# ad3.net
KiCad netlist of a schematic drawn in Altium Designer
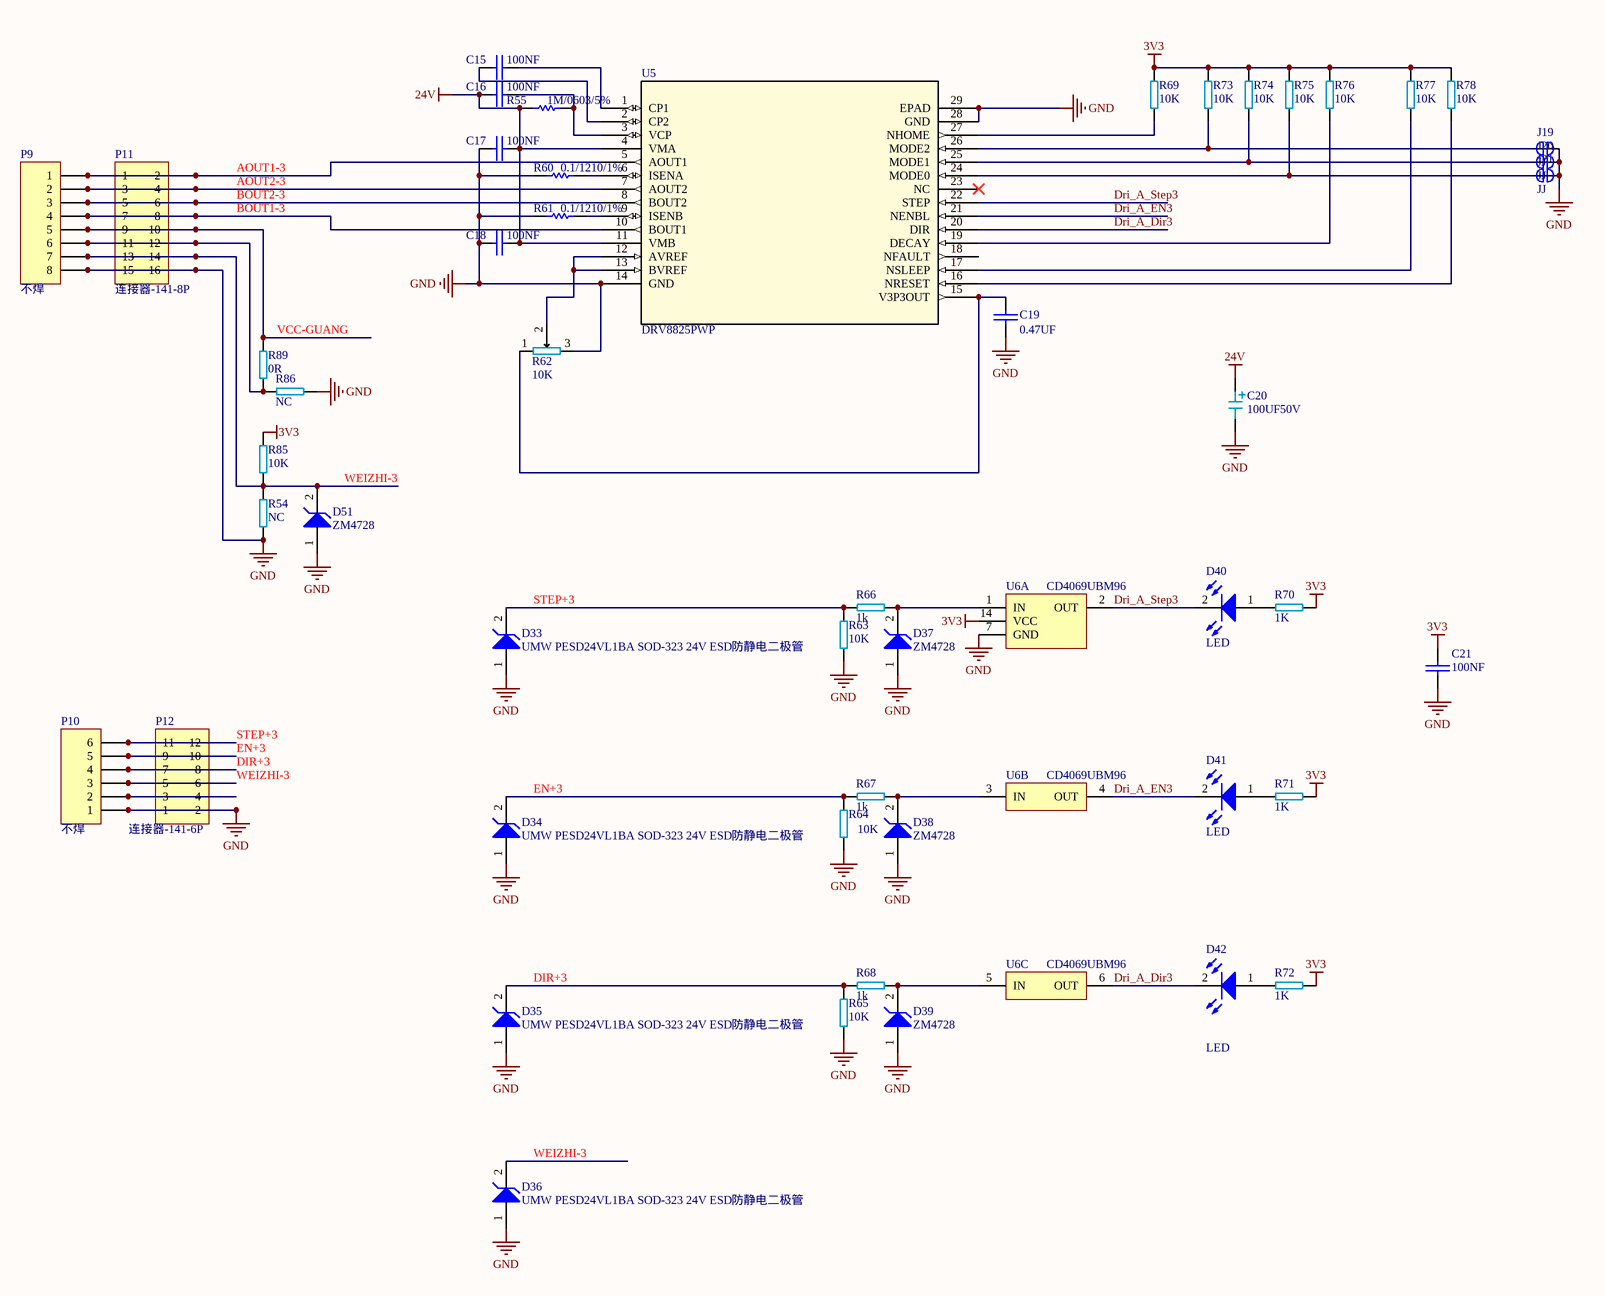
[diagram p0: ad3.SchDoc]

(export (version "E")
  (design (tool "Eeschema 10.0.6"))
  (components
    (comp (ref "C15")
      (value "100NF")
      (footprint "C0603")
      (description "Capacitor")
      (libsource (lib "Miscellaneous Devices") (part "CAP"))
    )
    (comp (ref "C16")
      (value "100NF")
      (footprint "C0603")
      (description "Capacitor")
      (libsource (lib "Miscellaneous Devices") (part "CAP"))
    )
    (comp (ref "C17")
      (value "100NF")
      (footprint "C0603")
      (description "Capacitor")
      (libsource (lib "Miscellaneous Devices") (part "CAP"))
    )
    (comp (ref "C18")
      (value "100NF")
      (footprint "C0603")
      (description "Capacitor")
      (libsource (lib "Miscellaneous Devices") (part "CAP"))
    )
    (comp (ref "C19")
      (value "0.47UF")
      (footprint "C0603")
      (description "Capacitor")
      (libsource (lib "Miscellaneous Devices") (part "CAP"))
    )
    (comp (ref "C20")
      (value "100UF50V")
      (footprint "CE8")
      (description "铝电解电容")
      (libsource (lib "base") (part "C+"))
    )
    (comp (ref "C21")
      (value "100NF")
      (footprint "C0603")
      (description "Capacitor")
      (libsource (lib "Miscellaneous Devices") (part "CAP"))
    )
    (comp (ref "D33")
      (value "UMW PESD24VL1BA SOD-323 24V ESD防静电二极管")
      (footprint "SOD323")
      (description "稳压管")
      (fields (field (name "PUBLISHER") "Altium Limited"))
      (libsource (lib "base") (part "TVS-SMA"))
    )
    (comp (ref "D34")
      (value "UMW PESD24VL1BA SOD-323 24V ESD防静电二极管")
      (footprint "SOD323")
      (description "稳压管")
      (fields (field (name "PUBLISHER") "Altium Limited"))
      (libsource (lib "base") (part "TVS-SMA"))
    )
    (comp (ref "D35")
      (value "UMW PESD24VL1BA SOD-323 24V ESD防静电二极管")
      (footprint "SOD323")
      (description "稳压管")
      (fields (field (name "PUBLISHER") "Altium Limited"))
      (libsource (lib "base") (part "TVS-SMA"))
    )
    (comp (ref "D36")
      (value "UMW PESD24VL1BA SOD-323 24V ESD防静电二极管")
      (footprint "SOD323")
      (description "稳压管")
      (fields (field (name "PUBLISHER") "Altium Limited"))
      (libsource (lib "base") (part "TVS-SMA"))
    )
    (comp (ref "D37")
      (value "ZM4728")
      (footprint "D1206")
      (description "稳压管")
      (fields (field (name "PUBLISHER") "Altium Limited"))
      (libsource (lib "base") (part "TVS-SMA"))
    )
    (comp (ref "D38")
      (value "ZM4728")
      (footprint "D1206")
      (description "稳压管")
      (fields (field (name "PUBLISHER") "Altium Limited"))
      (libsource (lib "base") (part "TVS-SMA"))
    )
    (comp (ref "D39")
      (value "ZM4728")
      (footprint "D1206")
      (description "稳压管")
      (fields (field (name "PUBLISHER") "Altium Limited"))
      (libsource (lib "base") (part "TVS-SMA"))
    )
    (comp (ref "D40")
      (value "LED")
      (footprint "LED0603")
      (description "LED0603")
      (fields (field (name "PUBLISHER") "Altium Limited"))
      (libsource (lib "base") (part "LED0603"))
    )
    (comp (ref "D41")
      (value "LED")
      (footprint "LED0603")
      (description "LED0603")
      (fields (field (name "PUBLISHER") "Altium Limited"))
      (libsource (lib "base") (part "LED0603"))
    )
    (comp (ref "D42")
      (value "LED")
      (footprint "LED0603")
      (description "LED0603")
      (fields (field (name "PUBLISHER") "Altium Limited"))
      (libsource (lib "base") (part "LED0603"))
    )
    (comp (ref "D51")
      (value "ZM4728")
      (footprint "D1206")
      (description "稳压管")
      (fields (field (name "PUBLISHER") "Altium Limited"))
      (libsource (lib "base") (part "TVS-SMA"))
    )
    (comp (ref "J19")
      (value "JJ")
      (footprint "TIAOXIAN-PAN")
      (description "跳线")
      (libsource (lib "base") (part "JJ"))
    )
    (comp (ref "J20")
      (value "JJ")
      (footprint "TIAOXIAN-PAN")
      (description "跳线")
      (libsource (lib "base") (part "JJ"))
    )
    (comp (ref "J21")
      (value "JJ")
      (footprint "TIAOXIAN-PAN")
      (description "跳线")
      (libsource (lib "base") (part "JJ"))
    )
    (comp (ref "P9")
      (value "不焊")
      (footprint "SIP8")
      (description "连接器")
      (fields (field (name "PUBLISHER") "Altium Limited"))
      (libsource (lib "base") (part "SIP8"))
    )
    (comp (ref "P10")
      (value "不焊")
      (footprint "SIP6")
      (description "连接器")
      (fields (field (name "PUBLISHER") "Altium Limited"))
      (libsource (lib "base") (part "SIP6"))
    )
    (comp (ref "P11")
      (value "连接器-141-8P")
      (footprint "141V-8P")
      (description "连接器")
      (fields (field (name "PUBLISHER") "Altium Limited"))
      (libsource (lib "base") (part "DIC16"))
    )
    (comp (ref "P12")
      (value "连接器-141-6P")
      (footprint "141V-6P")
      (description "连接器")
      (fields (field (name "PUBLISHER") "Altium Limited"))
      (libsource (lib "base") (part "DIC12"))
    )
    (comp (ref "R54")
      (value "NC")
      (footprint "R0603")
      (description "贴片电阻")
      (libsource (lib "base") (part "R-0603"))
    )
    (comp (ref "R55")
      (value "1M/0603/5%")
      (footprint "R0603")
      (description "Resistor")
      (fields (field (name "PUBLISHER") "Altium Limited"))
      (libsource (lib "Miscellaneous Devices") (part "Res1"))
    )
    (comp (ref "R60")
      (value "0.1/1210/1%")
      (footprint "R1210")
      (description "Resistor")
      (fields (field (name "PUBLISHER") "Altium Limited"))
      (libsource (lib "Miscellaneous Devices") (part "Res1"))
    )
    (comp (ref "R61")
      (value "0.1/1210/1%")
      (footprint "R1210")
      (description "Resistor")
      (fields (field (name "PUBLISHER") "Altium Limited"))
      (libsource (lib "Miscellaneous Devices") (part "Res1"))
    )
    (comp (ref "R62")
      (value "10K")
      (footprint "RR-MINI-SMD")
      (description "电位器")
      (libsource (lib "base") (part "RR"))
    )
    (comp (ref "R63")
      (value "10K")
      (footprint "R0603")
      (description "贴片电阻")
      (libsource (lib "base") (part "R-0603"))
    )
    (comp (ref "R64")
      (value "10K")
      (footprint "R0603")
      (description "贴片电阻")
      (libsource (lib "base") (part "R-0603"))
    )
    (comp (ref "R65")
      (value "10K")
      (footprint "R0603")
      (description "贴片电阻")
      (libsource (lib "base") (part "R-0603"))
    )
    (comp (ref "R66")
      (value "1k")
      (footprint "R0603")
      (description "贴片电阻")
      (libsource (lib "base") (part "R-0603"))
    )
    (comp (ref "R67")
      (value "1k")
      (footprint "R0603")
      (description "贴片电阻")
      (libsource (lib "base") (part "R-0603"))
    )
    (comp (ref "R68")
      (value "1k")
      (footprint "R0603")
      (description "贴片电阻")
      (libsource (lib "base") (part "R-0603"))
    )
    (comp (ref "R69")
      (value "10K")
      (footprint "R0603")
      (description "贴片电阻")
      (libsource (lib "base") (part "R-0603"))
    )
    (comp (ref "R70")
      (value "1K")
      (footprint "R0603")
      (description "贴片电阻")
      (libsource (lib "base") (part "R-0603"))
    )
    (comp (ref "R71")
      (value "1K")
      (footprint "R0603")
      (description "贴片电阻")
      (libsource (lib "base") (part "R-0603"))
    )
    (comp (ref "R72")
      (value "1K")
      (footprint "R0603")
      (description "贴片电阻")
      (libsource (lib "base") (part "R-0603"))
    )
    (comp (ref "R73")
      (value "10K")
      (footprint "R0603")
      (description "贴片电阻")
      (libsource (lib "base") (part "R-0603"))
    )
    (comp (ref "R74")
      (value "10K")
      (footprint "R0603")
      (description "贴片电阻")
      (libsource (lib "base") (part "R-0603"))
    )
    (comp (ref "R75")
      (value "10K")
      (footprint "R0603")
      (description "贴片电阻")
      (libsource (lib "base") (part "R-0603"))
    )
    (comp (ref "R76")
      (value "10K")
      (footprint "R0603")
      (description "贴片电阻")
      (libsource (lib "base") (part "R-0603"))
    )
    (comp (ref "R77")
      (value "10K")
      (footprint "R0603")
      (description "贴片电阻")
      (libsource (lib "base") (part "R-0603"))
    )
    (comp (ref "R78")
      (value "10K")
      (footprint "R0603")
      (description "贴片电阻")
      (libsource (lib "base") (part "R-0603"))
    )
    (comp (ref "R85")
      (value "10K")
      (footprint "R0603")
      (description "贴片电阻")
      (libsource (lib "base") (part "R-0603"))
    )
    (comp (ref "R86")
      (value "NC")
      (footprint "R0603")
      (description "贴片电阻")
      (libsource (lib "base") (part "R-0603"))
    )
    (comp (ref "R89")
      (value "0R")
      (footprint "R0603")
      (description "贴片电阻")
      (libsource (lib "base") (part "R-0603"))
    )
    (comp (ref "U5")
      (value "DRV8825PWP")
      (footprint "HTSSOP28")
      (description "芯片")
      (libsource (lib "User") (part "DRV8825PWP"))
    )
    (comp (ref "U6")
      (value "CD4069UBM96")
      (footprint "SO14")
      (description "芯片")
      (libsource (lib "Chip") (part "CD4069"))
    )
  )
  (nets
    (net (code "1") (name "/AOUT1-3") (class "Default")
      (node (ref "P11") (pin "1") (pinfunction "1_1") (pintype "passive"))
      (node (ref "P11") (pin "2") (pinfunction "2_2") (pintype "passive"))
      (node (ref "P9") (pin "1") (pinfunction "1_1") (pintype "passive"))
      (node (ref "U5") (pin "5") (pinfunction "AOUT1_5") (pintype "output"))
    )
    (net (code "2") (name "/AOUT2-3") (class "Default")
      (node (ref "P11") (pin "3") (pinfunction "3_3") (pintype "passive"))
      (node (ref "P11") (pin "4") (pinfunction "4_4") (pintype "passive"))
      (node (ref "P9") (pin "2") (pinfunction "2_2") (pintype "passive"))
      (node (ref "U5") (pin "7") (pinfunction "AOUT2_7") (pintype "output"))
    )
    (net (code "3") (name "/BOUT1-3") (class "Default")
      (node (ref "P11") (pin "7") (pinfunction "7_7") (pintype "passive"))
      (node (ref "P11") (pin "8") (pinfunction "8_8") (pintype "passive"))
      (node (ref "P9") (pin "4") (pinfunction "4_4") (pintype "passive"))
      (node (ref "U5") (pin "10") (pinfunction "BOUT1_10") (pintype "output"))
    )
    (net (code "4") (name "/BOUT2-3") (class "Default")
      (node (ref "P11") (pin "5") (pinfunction "5_5") (pintype "passive"))
      (node (ref "P11") (pin "6") (pinfunction "6_6") (pintype "passive"))
      (node (ref "P9") (pin "3") (pinfunction "3_3") (pintype "passive"))
      (node (ref "U5") (pin "8") (pinfunction "BOUT2_8") (pintype "output"))
    )
    (net (code "5") (name "/DIR+3") (class "Default")
      (node (ref "D35") (pin "2") (pinfunction "2_2") (pintype "passive"))
      (node (ref "P10") (pin "4") (pinfunction "4_4") (pintype "passive"))
      (node (ref "P12") (pin "7") (pinfunction "7_7") (pintype "passive"))
      (node (ref "P12") (pin "8") (pinfunction "8_8") (pintype "passive"))
      (node (ref "R65") (pin "2") (pinfunction "2_2") (pintype "passive"))
      (node (ref "R68") (pin "2") (pinfunction "2_2") (pintype "passive"))
    )
    (net (code "6") (name "/Dri_A_Dir3") (class "Default")
      (node (ref "D42") (pin "2") (pinfunction "K_2") (pintype "passive"))
      (node (ref "U5") (pin "20") (pinfunction "DIR_20") (pintype "input"))
      (node (ref "U6") (pin "6") (pinfunction "OUT_6") (pintype "passive"))
    )
    (net (code "7") (name "/Dri_A_EN3") (class "Default")
      (node (ref "D41") (pin "2") (pinfunction "K_2") (pintype "passive"))
      (node (ref "U5") (pin "21") (pinfunction "NENBL_21") (pintype "input"))
      (node (ref "U6") (pin "4") (pinfunction "OUT_4") (pintype "passive"))
    )
    (net (code "8") (name "/Dri_A_Step3") (class "Default")
      (node (ref "D40") (pin "2") (pinfunction "K_2") (pintype "passive"))
      (node (ref "U5") (pin "22") (pinfunction "STEP_22") (pintype "input"))
      (node (ref "U6") (pin "2") (pinfunction "OUT_2") (pintype "passive"))
    )
    (net (code "9") (name "/EN+3") (class "Default")
      (node (ref "D34") (pin "2") (pinfunction "2_2") (pintype "passive"))
      (node (ref "P10") (pin "5") (pinfunction "5_5") (pintype "passive"))
      (node (ref "P12") (pin "10") (pinfunction "10_10") (pintype "passive"))
      (node (ref "P12") (pin "9") (pinfunction "9_9") (pintype "passive"))
      (node (ref "R64") (pin "2") (pinfunction "2_2") (pintype "passive"))
      (node (ref "R67") (pin "2") (pinfunction "2_2") (pintype "passive"))
    )
    (net (code "10") (name "/STEP+3") (class "Default")
      (node (ref "D33") (pin "2") (pinfunction "2_2") (pintype "passive"))
      (node (ref "P10") (pin "6") (pinfunction "6_6") (pintype "passive"))
      (node (ref "P12") (pin "11") (pinfunction "11_11") (pintype "passive"))
      (node (ref "P12") (pin "12") (pinfunction "12_12") (pintype "passive"))
      (node (ref "R63") (pin "2") (pinfunction "2_2") (pintype "passive"))
      (node (ref "R66") (pin "2") (pinfunction "2_2") (pintype "passive"))
    )
    (net (code "11") (name "/VCC-GUANG") (class "Default")
      (node (ref "P11") (pin "10") (pinfunction "10_10") (pintype "passive"))
      (node (ref "P11") (pin "9") (pinfunction "9_9") (pintype "passive"))
      (node (ref "P9") (pin "5") (pinfunction "5_5") (pintype "passive"))
      (node (ref "R89") (pin "2") (pinfunction "2_2") (pintype "passive"))
    )
    (net (code "12") (name "/WEIZHI-3") (class "Default")
      (node (ref "D36") (pin "2") (pinfunction "2_2") (pintype "passive"))
      (node (ref "D51") (pin "2") (pinfunction "2_2") (pintype "passive"))
      (node (ref "P10") (pin "3") (pinfunction "3_3") (pintype "passive"))
      (node (ref "P11") (pin "13") (pinfunction "13_13") (pintype "passive"))
      (node (ref "P11") (pin "14") (pinfunction "14_14") (pintype "passive"))
      (node (ref "P12") (pin "5") (pinfunction "5_5") (pintype "passive"))
      (node (ref "P12") (pin "6") (pinfunction "6_6") (pintype "passive"))
      (node (ref "P9") (pin "7") (pinfunction "7_7") (pintype "passive"))
      (node (ref "R54") (pin "2") (pinfunction "2_2") (pintype "passive"))
      (node (ref "R85") (pin "1") (pinfunction "1_1") (pintype "passive"))
    )
    (net (code "13") (name "3V3") (class "Default")
      (node (ref "C21") (pin "2") (pinfunction "2_2") (pintype "passive"))
      (node (ref "R69") (pin "2") (pinfunction "2_2") (pintype "passive"))
      (node (ref "R70") (pin "2") (pinfunction "2_2") (pintype "passive"))
      (node (ref "R71") (pin "2") (pinfunction "2_2") (pintype "passive"))
      (node (ref "R72") (pin "2") (pinfunction "2_2") (pintype "passive"))
      (node (ref "R73") (pin "2") (pinfunction "2_2") (pintype "passive"))
      (node (ref "R74") (pin "2") (pinfunction "2_2") (pintype "passive"))
      (node (ref "R75") (pin "2") (pinfunction "2_2") (pintype "passive"))
      (node (ref "R76") (pin "2") (pinfunction "2_2") (pintype "passive"))
      (node (ref "R77") (pin "2") (pinfunction "2_2") (pintype "passive"))
      (node (ref "R78") (pin "2") (pinfunction "2_2") (pintype "passive"))
      (node (ref "R85") (pin "2") (pinfunction "2_2") (pintype "passive"))
      (node (ref "U6") (pin "14") (pinfunction "VCC_14") (pintype "passive"))
    )
    (net (code "14") (name "24V") (class "Default")
      (node (ref "C16") (pin "1") (pinfunction "1_1") (pintype "passive"))
      (node (ref "C17") (pin "2") (pinfunction "2_2") (pintype "passive"))
      (node (ref "C18") (pin "2") (pinfunction "2_2") (pintype "passive"))
      (node (ref "C20") (pin "1") (pinfunction "1_1") (pintype "passive"))
      (node (ref "R55") (pin "2") (pinfunction "2_2") (pintype "passive"))
      (node (ref "U5") (pin "11") (pinfunction "VMB_11") (pintype "power_in"))
      (node (ref "U5") (pin "4") (pinfunction "VMA_4") (pintype "power_in"))
    )
    (net (code "15") (name "GND") (class "Default")
      (node (ref "C17") (pin "1") (pinfunction "1_1") (pintype "passive"))
      (node (ref "C18") (pin "1") (pinfunction "1_1") (pintype "passive"))
      (node (ref "C19") (pin "1") (pinfunction "1_1") (pintype "passive"))
      (node (ref "C20") (pin "2") (pinfunction "2_2") (pintype "passive"))
      (node (ref "C21") (pin "1") (pinfunction "1_1") (pintype "passive"))
      (node (ref "D33") (pin "1") (pinfunction "1_1") (pintype "passive"))
      (node (ref "D34") (pin "1") (pinfunction "1_1") (pintype "passive"))
      (node (ref "D35") (pin "1") (pinfunction "1_1") (pintype "passive"))
      (node (ref "D36") (pin "1") (pinfunction "1_1") (pintype "passive"))
      (node (ref "D37") (pin "1") (pinfunction "1_1") (pintype "passive"))
      (node (ref "D38") (pin "1") (pinfunction "1_1") (pintype "passive"))
      (node (ref "D39") (pin "1") (pinfunction "1_1") (pintype "passive"))
      (node (ref "D51") (pin "1") (pinfunction "1_1") (pintype "passive"))
      (node (ref "J19") (pin "2") (pinfunction "2_2") (pintype "passive"))
      (node (ref "J20") (pin "2") (pinfunction "2_2") (pintype "passive"))
      (node (ref "J21") (pin "2") (pinfunction "2_2") (pintype "passive"))
      (node (ref "P10") (pin "1") (pinfunction "1_1") (pintype "passive"))
      (node (ref "P11") (pin "15") (pinfunction "15_15") (pintype "passive"))
      (node (ref "P11") (pin "16") (pinfunction "16_16") (pintype "passive"))
      (node (ref "P12") (pin "1") (pinfunction "1_1") (pintype "passive"))
      (node (ref "P12") (pin "2") (pinfunction "2_2") (pintype "passive"))
      (node (ref "P9") (pin "8") (pinfunction "8_8") (pintype "passive"))
      (node (ref "R54") (pin "1") (pinfunction "1_1") (pintype "passive"))
      (node (ref "R60") (pin "2") (pinfunction "2_2") (pintype "passive"))
      (node (ref "R61") (pin "2") (pinfunction "2_2") (pintype "passive"))
      (node (ref "R62") (pin "3") (pinfunction "3_3") (pintype "passive"))
      (node (ref "R63") (pin "1") (pinfunction "1_1") (pintype "passive"))
      (node (ref "R64") (pin "1") (pinfunction "1_1") (pintype "passive"))
      (node (ref "R65") (pin "1") (pinfunction "1_1") (pintype "passive"))
      (node (ref "R86") (pin "1") (pinfunction "1_1") (pintype "passive"))
      (node (ref "U5") (pin "14") (pinfunction "GND_14") (pintype "power_in"))
      (node (ref "U5") (pin "28") (pinfunction "GND_28") (pintype "power_in"))
      (node (ref "U5") (pin "29") (pinfunction "EPAD_29") (pintype "passive"))
      (node (ref "U6") (pin "7") (pinfunction "GND_7") (pintype "passive"))
    )
    (net (code "16") (name "Net-(D40-A)") (class "Default")
      (node (ref "D40") (pin "1") (pinfunction "A_1") (pintype "passive"))
      (node (ref "R70") (pin "1") (pinfunction "1_1") (pintype "passive"))
    )
    (net (code "17") (name "Net-(D41-A)") (class "Default")
      (node (ref "D41") (pin "1") (pinfunction "A_1") (pintype "passive"))
      (node (ref "R71") (pin "1") (pinfunction "1_1") (pintype "passive"))
    )
    (net (code "18") (name "Net-(D42-A)") (class "Default")
      (node (ref "D42") (pin "1") (pinfunction "A_1") (pintype "passive"))
      (node (ref "R72") (pin "1") (pinfunction "1_1") (pintype "passive"))
    )
    (net (code "19") (name "Net-(P10-Pad2)") (class "Default")
      (node (ref "P10") (pin "2") (pinfunction "2_2") (pintype "passive"))
      (node (ref "P12") (pin "3") (pinfunction "3_3") (pintype "passive"))
      (node (ref "P12") (pin "4") (pinfunction "4_4") (pintype "passive"))
    )
    (net (code "20") (name "Net-(P11-Pad11)") (class "Default")
      (node (ref "P11") (pin "11") (pinfunction "11_11") (pintype "passive"))
      (node (ref "P11") (pin "12") (pinfunction "12_12") (pintype "passive"))
      (node (ref "P9") (pin "6") (pinfunction "6_6") (pintype "passive"))
      (node (ref "R86") (pin "2") (pinfunction "2_2") (pintype "passive"))
      (node (ref "R89") (pin "1") (pinfunction "1_1") (pintype "passive"))
    )
    (net (code "21") (name "Net-(U5-AVREF)") (class "Default")
      (node (ref "R62") (pin "2") (pinfunction "2_2") (pintype "passive"))
      (node (ref "U5") (pin "12") (pinfunction "AVREF_12") (pintype "input"))
      (node (ref "U5") (pin "13") (pinfunction "BVREF_13") (pintype "input"))
    )
    (net (code "22") (name "Net-(U5-CP1)") (class "Default")
      (node (ref "C15") (pin "2") (pinfunction "2_2") (pintype "passive"))
      (node (ref "U5") (pin "1") (pinfunction "CP1_1") (pintype "bidirectional"))
    )
    (net (code "23") (name "Net-(U5-CP2)") (class "Default")
      (node (ref "C15") (pin "1") (pinfunction "1_1") (pintype "passive"))
      (node (ref "U5") (pin "2") (pinfunction "CP2_2") (pintype "bidirectional"))
    )
    (net (code "24") (name "Net-(U5-DECAY)") (class "Default")
      (node (ref "R76") (pin "1") (pinfunction "1_1") (pintype "passive"))
      (node (ref "U5") (pin "19") (pinfunction "DECAY_19") (pintype "input"))
    )
    (net (code "25") (name "Net-(U5-ISENA)") (class "Default")
      (node (ref "R60") (pin "1") (pinfunction "1_1") (pintype "passive"))
      (node (ref "U5") (pin "6") (pinfunction "ISENA_6") (pintype "bidirectional"))
    )
    (net (code "26") (name "Net-(U5-ISENB)") (class "Default")
      (node (ref "R61") (pin "1") (pinfunction "1_1") (pintype "passive"))
      (node (ref "U5") (pin "9") (pinfunction "ISENB_9") (pintype "bidirectional"))
    )
    (net (code "27") (name "Net-(U5-MODE0)") (class "Default")
      (node (ref "J21") (pin "1") (pinfunction "1_1") (pintype "passive"))
      (node (ref "R75") (pin "1") (pinfunction "1_1") (pintype "passive"))
      (node (ref "U5") (pin "24") (pinfunction "MODE0_24") (pintype "input"))
    )
    (net (code "28") (name "Net-(U5-MODE1)") (class "Default")
      (node (ref "J20") (pin "1") (pinfunction "1_1") (pintype "passive"))
      (node (ref "R74") (pin "1") (pinfunction "1_1") (pintype "passive"))
      (node (ref "U5") (pin "25") (pinfunction "MODE1_25") (pintype "input"))
    )
    (net (code "29") (name "Net-(U5-MODE2)") (class "Default")
      (node (ref "J19") (pin "1") (pinfunction "1_1") (pintype "passive"))
      (node (ref "R73") (pin "1") (pinfunction "1_1") (pintype "passive"))
      (node (ref "U5") (pin "26") (pinfunction "MODE2_26") (pintype "input"))
    )
    (net (code "30") (name "Net-(U5-NHOME)") (class "Default")
      (node (ref "R69") (pin "1") (pinfunction "1_1") (pintype "passive"))
      (node (ref "U5") (pin "27") (pinfunction "NHOME_27") (pintype "output"))
    )
    (net (code "31") (name "Net-(U5-NRESET)") (class "Default")
      (node (ref "R78") (pin "1") (pinfunction "1_1") (pintype "passive"))
      (node (ref "U5") (pin "16") (pinfunction "NRESET_16") (pintype "input"))
    )
    (net (code "32") (name "Net-(U5-NSLEEP)") (class "Default")
      (node (ref "R77") (pin "1") (pinfunction "1_1") (pintype "passive"))
      (node (ref "U5") (pin "17") (pinfunction "NSLEEP_17") (pintype "input"))
    )
    (net (code "33") (name "Net-(U5-V3P3OUT)") (class "Default")
      (node (ref "C19") (pin "2") (pinfunction "2_2") (pintype "passive"))
      (node (ref "R62") (pin "1") (pinfunction "1_1") (pintype "passive"))
      (node (ref "U5") (pin "15") (pinfunction "V3P3OUT_15") (pintype "output"))
    )
    (net (code "34") (name "Net-(U5-VCP)") (class "Default")
      (node (ref "C16") (pin "2") (pinfunction "2_2") (pintype "passive"))
      (node (ref "R55") (pin "1") (pinfunction "1_1") (pintype "passive"))
      (node (ref "U5") (pin "3") (pinfunction "VCP_3") (pintype "bidirectional"))
    )
    (net (code "35") (name "Net-(U6A-IN)") (class "Default")
      (node (ref "D37") (pin "2") (pinfunction "2_2") (pintype "passive"))
      (node (ref "R66") (pin "1") (pinfunction "1_1") (pintype "passive"))
      (node (ref "U6") (pin "1") (pinfunction "IN_1") (pintype "passive"))
    )
    (net (code "36") (name "Net-(U6B-IN)") (class "Default")
      (node (ref "D38") (pin "2") (pinfunction "2_2") (pintype "passive"))
      (node (ref "R67") (pin "1") (pinfunction "1_1") (pintype "passive"))
      (node (ref "U6") (pin "3") (pinfunction "IN_3") (pintype "passive"))
    )
    (net (code "37") (name "Net-(U6C-IN)") (class "Default")
      (node (ref "D39") (pin "2") (pinfunction "2_2") (pintype "passive"))
      (node (ref "R68") (pin "1") (pinfunction "1_1") (pintype "passive"))
      (node (ref "U6") (pin "5") (pinfunction "IN_5") (pintype "passive"))
    )
    (net (code "38") (name "unconnected-(U5-NC-Pad23)") (class "Default")
      (node (ref "U5") (pin "23") (pinfunction "NC_23") (pintype "passive+no_connect"))
    )
    (net (code "39") (name "unconnected-(U5-NFAULT-Pad18)") (class "Default")
      (node (ref "U5") (pin "18") (pinfunction "NFAULT_18") (pintype "output"))
    )
  )
)
